# Servo_driver.net
KiCad netlist of a schematic drawn in EAGLE
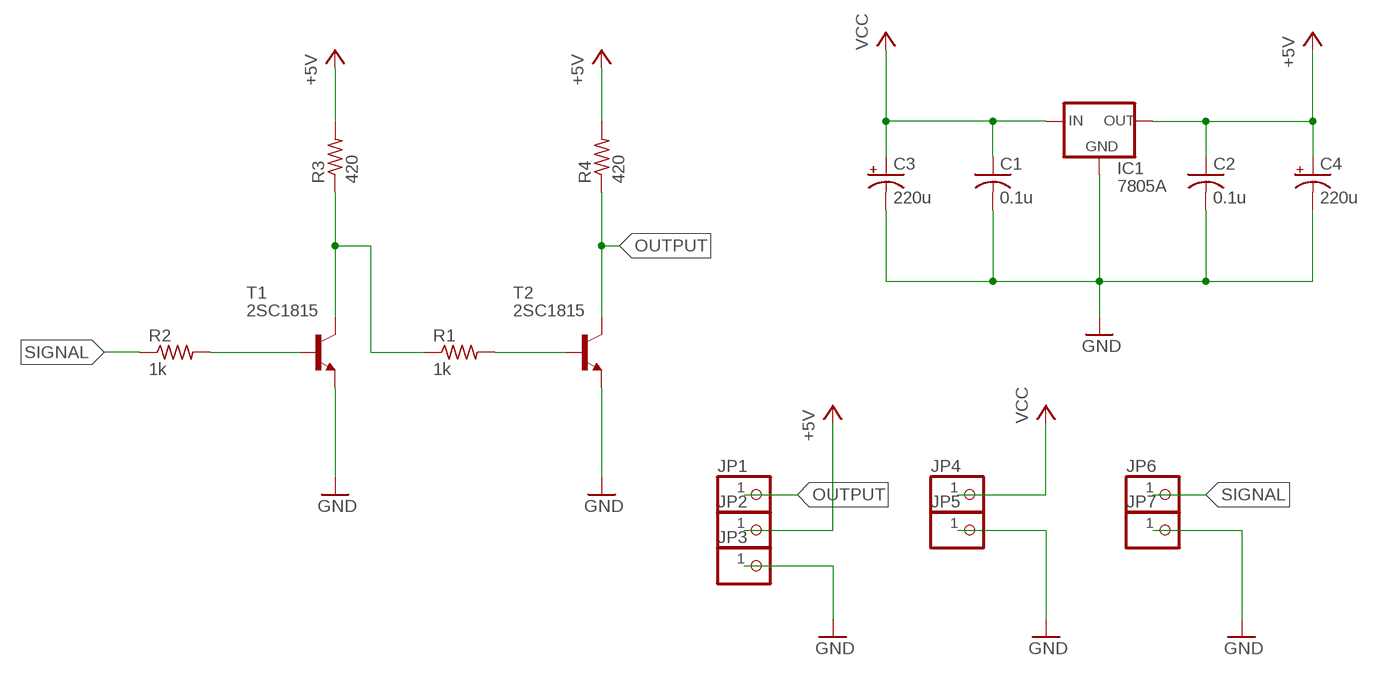
[diagram p0: schematic, sheet 1]

(export (version "E")
  (design (tool "Eeschema 10.0.6"))
  (components
    (comp (ref "C1")
      (value "0.1u")
      (footprint "eagle-import:C050-024X044")
      (libsource (lib "eagle-import") (part "C-US050-024X044"))
    )
    (comp (ref "C2")
      (value "0.1u")
      (footprint "eagle-import:C050-024X044")
      (libsource (lib "eagle-import") (part "C-US050-024X044"))
    )
    (comp (ref "C3")
      (value "220u")
      (footprint "eagle-import:E2,5-6")
      (libsource (lib "eagle-import") (part "CPOL-USE2.5-6"))
    )
    (comp (ref "C4")
      (value "220u")
      (footprint "eagle-import:E2,5-6")
      (libsource (lib "eagle-import") (part "CPOL-USE2.5-6"))
    )
    (comp (ref "IC1")
      (value "7805A")
      (footprint "eagle-import:78XXS")
      (libsource (lib "eagle-import") (part "78XXS"))
    )
    (comp (ref "JP1")
      (value "PINHD-1X1")
      (footprint "eagle-import:1X01")
      (libsource (lib "eagle-import") (part "PINHD-1X1"))
    )
    (comp (ref "JP2")
      (value "PINHD-1X1")
      (footprint "eagle-import:1X01")
      (libsource (lib "eagle-import") (part "PINHD-1X1"))
    )
    (comp (ref "JP3")
      (value "PINHD-1X1")
      (footprint "eagle-import:1X01")
      (libsource (lib "eagle-import") (part "PINHD-1X1"))
    )
    (comp (ref "JP4")
      (value "PINHD-1X1")
      (footprint "eagle-import:1X01")
      (libsource (lib "eagle-import") (part "PINHD-1X1"))
    )
    (comp (ref "JP5")
      (value "PINHD-1X1")
      (footprint "eagle-import:1X01")
      (libsource (lib "eagle-import") (part "PINHD-1X1"))
    )
    (comp (ref "JP6")
      (value "PINHD-1X1")
      (footprint "eagle-import:1X01")
      (libsource (lib "eagle-import") (part "PINHD-1X1"))
    )
    (comp (ref "JP7")
      (value "PINHD-1X1")
      (footprint "eagle-import:1X01")
      (libsource (lib "eagle-import") (part "PINHD-1X1"))
    )
    (comp (ref "R1")
      (value "1k")
      (footprint "eagle-import:0204_7")
      (libsource (lib "eagle-import") (part "R-US_0204/7"))
    )
    (comp (ref "R2")
      (value "1k")
      (footprint "eagle-import:0204_7")
      (libsource (lib "eagle-import") (part "R-US_0204/7"))
    )
    (comp (ref "R3")
      (value "420")
      (footprint "eagle-import:0204_7")
      (libsource (lib "eagle-import") (part "R-US_0204/7"))
    )
    (comp (ref "R4")
      (value "420")
      (footprint "eagle-import:0204_7")
      (libsource (lib "eagle-import") (part "R-US_0204/7"))
    )
    (comp (ref "T1")
      (value "2SC1815")
      (footprint "eagle-import:TO92-ECB")
      (libsource (lib "eagle-import") (part "2SC1815"))
    )
    (comp (ref "T2")
      (value "2SC1815")
      (footprint "eagle-import:TO92-ECB")
      (libsource (lib "eagle-import") (part "2SC1815"))
    )
  )
  (nets
    (net (code "1") (name "+5V") (class "Default")
      (node (ref "C2") (pin "1") (pinfunction "1_1") (pintype "passive"))
      (node (ref "C4") (pin "+") (pinfunction "+_+") (pintype "passive"))
      (node (ref "IC1") (pin "OUT") (pinfunction "OUT_OUT") (pintype "passive"))
      (node (ref "JP2") (pin "1") (pinfunction "1_1") (pintype "passive"))
      (node (ref "R3") (pin "2") (pinfunction "2_2") (pintype "passive"))
      (node (ref "R4") (pin "2") (pinfunction "2_2") (pintype "passive"))
    )
    (net (code "2") (name "GND") (class "Default")
      (node (ref "C1") (pin "2") (pinfunction "2_2") (pintype "passive"))
      (node (ref "C2") (pin "2") (pinfunction "2_2") (pintype "passive"))
      (node (ref "C3") (pin "-") (pinfunction "-_-") (pintype "passive"))
      (node (ref "C4") (pin "-") (pinfunction "-_-") (pintype "passive"))
      (node (ref "IC1") (pin "GND") (pinfunction "GND_GND") (pintype "input"))
      (node (ref "JP3") (pin "1") (pinfunction "1_1") (pintype "passive"))
      (node (ref "JP5") (pin "1") (pinfunction "1_1") (pintype "passive"))
      (node (ref "JP7") (pin "1") (pinfunction "1_1") (pintype "passive"))
      (node (ref "T1") (pin "E") (pinfunction "E_E") (pintype "passive"))
      (node (ref "T2") (pin "E") (pinfunction "E_E") (pintype "passive"))
    )
    (net (code "3") (name "Net-(R1-Pad1)") (class "Default")
      (node (ref "R1") (pin "1") (pinfunction "1_1") (pintype "passive"))
      (node (ref "R3") (pin "1") (pinfunction "1_1") (pintype "passive"))
      (node (ref "T1") (pin "C") (pinfunction "C_C") (pintype "passive"))
    )
    (net (code "4") (name "Net-(R1-Pad2)") (class "Default")
      (node (ref "R1") (pin "2") (pinfunction "2_2") (pintype "passive"))
      (node (ref "T2") (pin "B") (pinfunction "B_B") (pintype "passive"))
    )
    (net (code "5") (name "Net-(R2-Pad2)") (class "Default")
      (node (ref "R2") (pin "2") (pinfunction "2_2") (pintype "passive"))
      (node (ref "T1") (pin "B") (pinfunction "B_B") (pintype "passive"))
    )
    (net (code "6") (name "OUTPUT") (class "Default")
      (node (ref "JP1") (pin "1") (pinfunction "1_1") (pintype "passive"))
      (node (ref "R4") (pin "1") (pinfunction "1_1") (pintype "passive"))
      (node (ref "T2") (pin "C") (pinfunction "C_C") (pintype "passive"))
    )
    (net (code "7") (name "SIGNAL") (class "Default")
      (node (ref "JP6") (pin "1") (pinfunction "1_1") (pintype "passive"))
      (node (ref "R2") (pin "1") (pinfunction "1_1") (pintype "passive"))
    )
    (net (code "8") (name "VCC") (class "Default")
      (node (ref "C1") (pin "1") (pinfunction "1_1") (pintype "passive"))
      (node (ref "C3") (pin "+") (pinfunction "+_+") (pintype "passive"))
      (node (ref "IC1") (pin "IN") (pinfunction "IN_IN") (pintype "input"))
      (node (ref "JP4") (pin "1") (pinfunction "1_1") (pintype "passive"))
    )
  )
)
